# Audio_Input_Line_In.net
KiCad netlist of a schematic drawn in Altium Designer
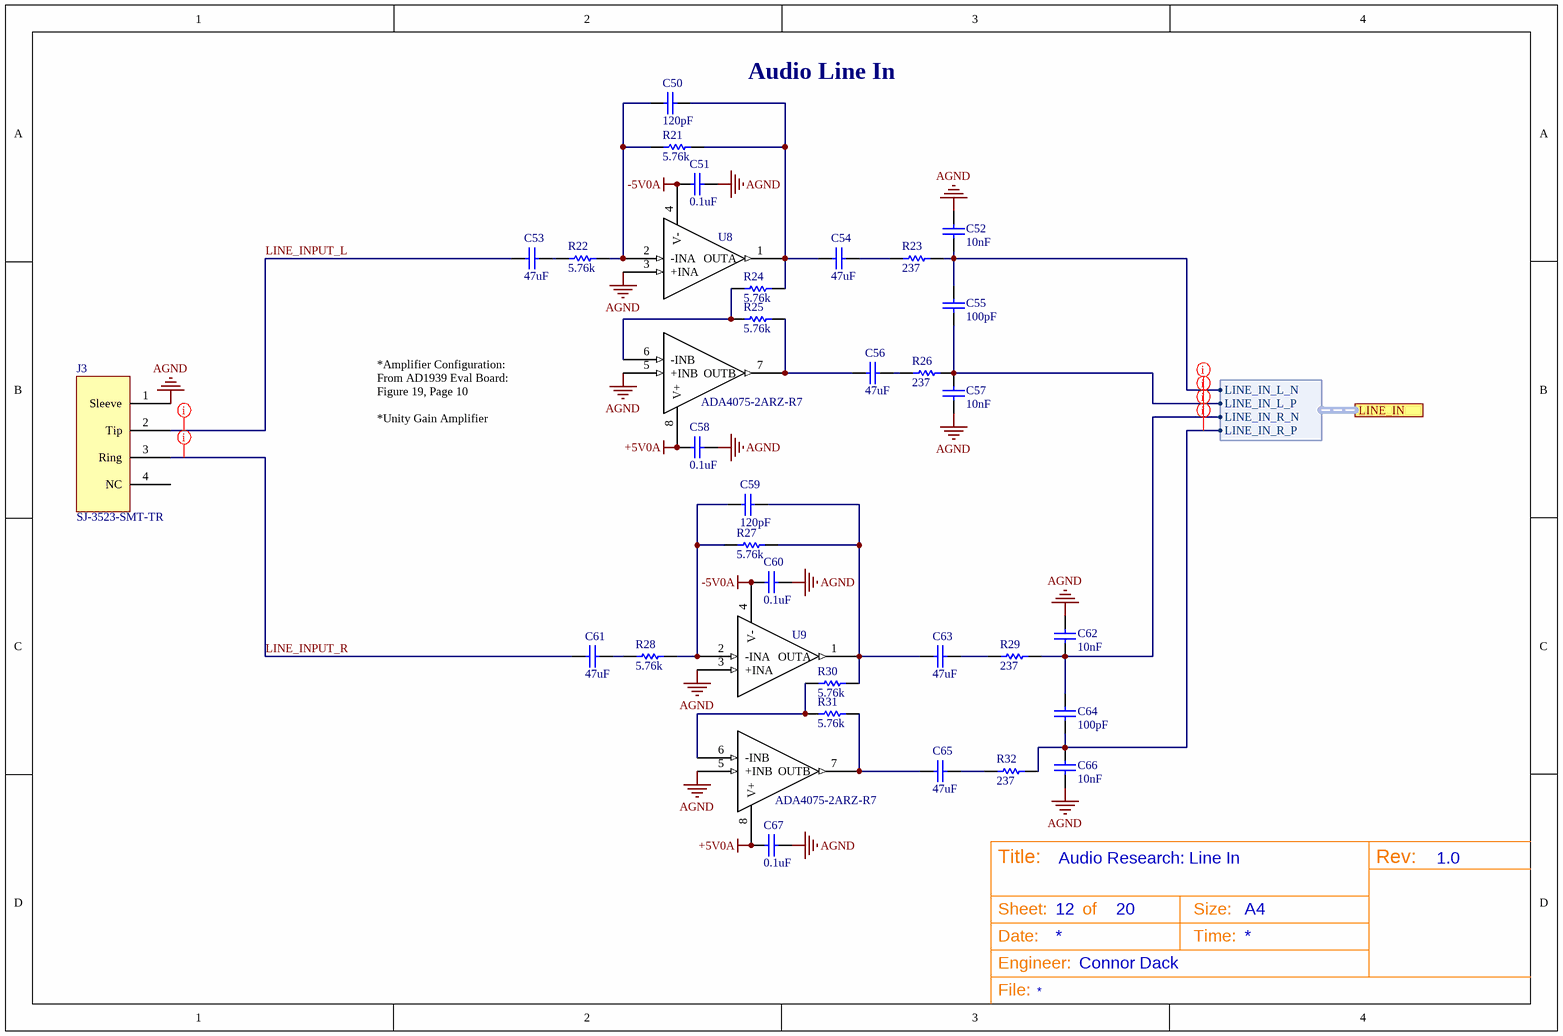
[diagram p0: Audio_Input_Line_In.SchDoc]

(export (version "E")
  (design (tool "Eeschema 10.0.6"))
  (components
    (comp (ref "C50")
      (value "CL10C121JB8NCNC")
      (footprint "3-0603_L")
      (description "120pF 50V Ceramic Capacitor C0G, NP0 0603 (1608 Metric) 0.063\" L x 0.031\" W (1.60mm x 0.80mm)")
      (fields
        (field (name "MANUFACTURER") "Samsung Electro-Mechanics America, Inc.")
        (field (name "TOLERANCE") "±5%")
        (field (name "CAPACITANCE") "120pF")
      )
      (libsource (lib "Schematic_Components") (part "CL10C121JB8NCNC"))
    )
    (comp (ref "C51")
      (value "CL10F104ZO8NNNC")
      (footprint "3-0603_L")
      (description "CAP CER 0.1UF 16V Y5V 0603")
      (fields
        (field (name "MANUFACTURER") "Samsung")
        (field (name "TOLERANCE") "80%")
        (field (name "CAPACITANCE") "0.1uF")
      )
      (libsource (lib "Schematic_Components_CD") (part "CL10F104ZO8NNNC"))
    )
    (comp (ref "C52")
      (value "~")
      (footprint "3-0603_L")
      (description "CAP CER 10000PF 200V X7R 0603")
      (fields
        (field (name "MANUFACTURER") "KEMET")
        (field (name "MANUFACTURER PART NUMBER") "C0603C103J2RACTU")
        (field (name "CAPACITANCE") "10nF")
      )
      (libsource (lib "Miscellaneous Devices") (part "C0603C103J2RACTU"))
    )
    (comp (ref "C53")
      (value "CL32A476KOJNNNE")
      (footprint "C1210X25_L")
      (description "CAP CER 47UF 16V X5R 1210")
      (fields
        (field (name "MANUFACTURER") "Samsung")
        (field (name "TOLERANCE") "10%")
        (field (name "CAPACITANCE") "47uF")
      )
      (libsource (lib "Schematic_Components_CD") (part "CL32A476KOJNNNE"))
    )
    (comp (ref "C54")
      (value "CL32A476KOJNNNE")
      (footprint "C1210X25_L")
      (description "CAP CER 47UF 16V X5R 1210")
      (fields
        (field (name "MANUFACTURER") "Samsung")
        (field (name "TOLERANCE") "10%")
        (field (name "CAPACITANCE") "47uF")
      )
      (libsource (lib "Schematic_Components_CD") (part "CL32A476KOJNNNE"))
    )
    (comp (ref "C55")
      (value "C1608C0G2A101J")
      (footprint "3-0603_L")
      (description "CAP CER 100PF 100V 5% NP0 0603")
      (fields
        (field (name "MANUFACTURER") "TDK Corporation")
        (field (name "TOLERANCE") "±5%")
        (field (name "CAPACITANCE") "100pF")
      )
      (libsource (lib "Schematic_Components") (part "C1608C0G2A101J"))
    )
    (comp (ref "C56")
      (value "CL32A476KOJNNNE")
      (footprint "C1210X25_L")
      (description "CAP CER 47UF 16V X5R 1210")
      (fields
        (field (name "MANUFACTURER") "Samsung")
        (field (name "TOLERANCE") "10%")
        (field (name "CAPACITANCE") "47uF")
      )
      (libsource (lib "Schematic_Components_CD") (part "CL32A476KOJNNNE"))
    )
    (comp (ref "C57")
      (value "~")
      (footprint "3-0603_L")
      (description "CAP CER 10000PF 200V X7R 0603")
      (fields
        (field (name "MANUFACTURER") "KEMET")
        (field (name "MANUFACTURER PART NUMBER") "C0603C103J2RACTU")
        (field (name "CAPACITANCE") "10nF")
      )
      (libsource (lib "Miscellaneous Devices") (part "C0603C103J2RACTU"))
    )
    (comp (ref "C58")
      (value "CL10F104ZO8NNNC")
      (footprint "3-0603_L")
      (description "CAP CER 0.1UF 16V Y5V 0603")
      (fields
        (field (name "MANUFACTURER") "Samsung")
        (field (name "TOLERANCE") "80%")
        (field (name "CAPACITANCE") "0.1uF")
      )
      (libsource (lib "Schematic_Components_CD") (part "CL10F104ZO8NNNC"))
    )
    (comp (ref "C59")
      (value "CL10C121JB8NCNC")
      (footprint "3-0603_L")
      (description "120pF 50V Ceramic Capacitor C0G, NP0 0603 (1608 Metric) 0.063\" L x 0.031\" W (1.60mm x 0.80mm)")
      (fields
        (field (name "MANUFACTURER") "Samsung Electro-Mechanics America, Inc.")
        (field (name "TOLERANCE") "±5%")
        (field (name "CAPACITANCE") "120pF")
      )
      (libsource (lib "Schematic_Components") (part "CL10C121JB8NCNC"))
    )
    (comp (ref "C60")
      (value "CL10F104ZO8NNNC")
      (footprint "3-0603_L")
      (description "CAP CER 0.1UF 16V Y5V 0603")
      (fields
        (field (name "MANUFACTURER") "Samsung")
        (field (name "TOLERANCE") "80%")
        (field (name "CAPACITANCE") "0.1uF")
      )
      (libsource (lib "Schematic_Components_CD") (part "CL10F104ZO8NNNC"))
    )
    (comp (ref "C61")
      (value "CL32A476KOJNNNE")
      (footprint "C1210X25_L")
      (description "CAP CER 47UF 16V X5R 1210")
      (fields
        (field (name "MANUFACTURER") "Samsung")
        (field (name "TOLERANCE") "10%")
        (field (name "CAPACITANCE") "47uF")
      )
      (libsource (lib "Schematic_Components_CD") (part "CL32A476KOJNNNE"))
    )
    (comp (ref "C62")
      (value "~")
      (footprint "3-0603_L")
      (description "CAP CER 10000PF 200V X7R 0603")
      (fields
        (field (name "MANUFACTURER") "KEMET")
        (field (name "MANUFACTURER PART NUMBER") "C0603C103J2RACTU")
        (field (name "CAPACITANCE") "10nF")
      )
      (libsource (lib "Miscellaneous Devices") (part "C0603C103J2RACTU"))
    )
    (comp (ref "C63")
      (value "CL32A476KOJNNNE")
      (footprint "C1210X25_L")
      (description "CAP CER 47UF 16V X5R 1210")
      (fields
        (field (name "MANUFACTURER") "Samsung")
        (field (name "TOLERANCE") "10%")
        (field (name "CAPACITANCE") "47uF")
      )
      (libsource (lib "Schematic_Components_CD") (part "CL32A476KOJNNNE"))
    )
    (comp (ref "C64")
      (value "C1608C0G2A101J")
      (footprint "3-0603_L")
      (description "CAP CER 100PF 100V 5% NP0 0603")
      (fields
        (field (name "MANUFACTURER") "TDK Corporation")
        (field (name "TOLERANCE") "±5%")
        (field (name "CAPACITANCE") "100pF")
      )
      (libsource (lib "Schematic_Components") (part "C1608C0G2A101J"))
    )
    (comp (ref "C65")
      (value "CL32A476KOJNNNE")
      (footprint "C1210X25_L")
      (description "CAP CER 47UF 16V X5R 1210")
      (fields
        (field (name "MANUFACTURER") "Samsung")
        (field (name "TOLERANCE") "10%")
        (field (name "CAPACITANCE") "47uF")
      )
      (libsource (lib "Schematic_Components_CD") (part "CL32A476KOJNNNE"))
    )
    (comp (ref "C66")
      (value "~")
      (footprint "3-0603_L")
      (description "CAP CER 10000PF 200V X7R 0603")
      (fields
        (field (name "MANUFACTURER") "KEMET")
        (field (name "MANUFACTURER PART NUMBER") "C0603C103J2RACTU")
        (field (name "CAPACITANCE") "10nF")
      )
      (libsource (lib "Miscellaneous Devices") (part "C0603C103J2RACTU"))
    )
    (comp (ref "C67")
      (value "CL10F104ZO8NNNC")
      (footprint "3-0603_L")
      (description "CAP CER 0.1UF 16V Y5V 0603")
      (fields
        (field (name "MANUFACTURER") "Samsung")
        (field (name "TOLERANCE") "80%")
        (field (name "CAPACITANCE") "0.1uF")
      )
      (libsource (lib "Schematic_Components_CD") (part "CL10F104ZO8NNNC"))
    )
    (comp (ref "J3")
      (value "SJ-3523-SMT-TR")
      (footprint "SJ-3523-SMT-TR")
      (description "3.50mm (0.141\", 1/8\", Mini Plug) - Headphone Phone Jack Stereo Connector Solder")
      (fields
        (field (name "MANUFACTURER") "CUI Inc.")
        (field (name "MANUFACTURER PART NUMBER") "SJ-3523-SMT-TR")
        (field (name "PUBLISHER") "Altium Limited")
      )
      (libsource (lib "NIH_DE0_Nano_Daughter_Card_Library") (part "SJ-3523-SMT-TR"))
    )
    (comp (ref "R21")
      (value "ERJ-3EKF5761V")
      (footprint "3-0603_R_L")
      (description "RES SMD 5.76K OHM 1% 1/10W 0603")
      (fields
        (field (name "MANUFACTURER") "Panasonic Electronic Components")
        (field (name "TOLERANCE") "±1%")
        (field (name "RESISTANCE (OHMS)") "5.76k")
      )
      (libsource (lib "Schematic_Components") (part "ERJ-3EKF5761V"))
    )
    (comp (ref "R22")
      (value "ERJ-3EKF5761V")
      (footprint "3-0603_R_L")
      (description "RES SMD 5.76K OHM 1% 1/10W 0603")
      (fields
        (field (name "MANUFACTURER") "Panasonic Electronic Components")
        (field (name "TOLERANCE") "±1%")
        (field (name "RESISTANCE (OHMS)") "5.76k")
      )
      (libsource (lib "Schematic_Components") (part "ERJ-3EKF5761V"))
    )
    (comp (ref "R23")
      (value "ERJ-3EKF2370V")
      (footprint "3-0603_R_L")
      (description "RES SMD 237 OHM 1% 1/10W 0603")
      (fields
        (field (name "MANUFACTURER") "Panasonic Electronic Components")
        (field (name "TOLERANCE") "±1%")
        (field (name "RESISTANCE (OHMS)") "237")
      )
      (libsource (lib "Schematic_Components") (part "ERJ-3EKF2370V"))
    )
    (comp (ref "R24")
      (value "ERJ-3EKF5761V")
      (footprint "3-0603_R_L")
      (description "RES SMD 5.76K OHM 1% 1/10W 0603")
      (fields
        (field (name "MANUFACTURER") "Panasonic Electronic Components")
        (field (name "TOLERANCE") "±1%")
        (field (name "RESISTANCE (OHMS)") "5.76k")
      )
      (libsource (lib "Schematic_Components") (part "ERJ-3EKF5761V"))
    )
    (comp (ref "R25")
      (value "ERJ-3EKF5761V")
      (footprint "3-0603_R_L")
      (description "RES SMD 5.76K OHM 1% 1/10W 0603")
      (fields
        (field (name "MANUFACTURER") "Panasonic Electronic Components")
        (field (name "TOLERANCE") "±1%")
        (field (name "RESISTANCE (OHMS)") "5.76k")
      )
      (libsource (lib "Schematic_Components") (part "ERJ-3EKF5761V"))
    )
    (comp (ref "R26")
      (value "ERJ-3EKF2370V")
      (footprint "3-0603_R_L")
      (description "RES SMD 237 OHM 1% 1/10W 0603")
      (fields
        (field (name "MANUFACTURER") "Panasonic Electronic Components")
        (field (name "TOLERANCE") "±1%")
        (field (name "RESISTANCE (OHMS)") "237")
      )
      (libsource (lib "Schematic_Components") (part "ERJ-3EKF2370V"))
    )
    (comp (ref "R27")
      (value "ERJ-3EKF5761V")
      (footprint "3-0603_R_L")
      (description "RES SMD 5.76K OHM 1% 1/10W 0603")
      (fields
        (field (name "MANUFACTURER") "Panasonic Electronic Components")
        (field (name "TOLERANCE") "±1%")
        (field (name "RESISTANCE (OHMS)") "5.76k")
      )
      (libsource (lib "Schematic_Components") (part "ERJ-3EKF5761V"))
    )
    (comp (ref "R28")
      (value "ERJ-3EKF5761V")
      (footprint "3-0603_R_L")
      (description "RES SMD 5.76K OHM 1% 1/10W 0603")
      (fields
        (field (name "MANUFACTURER") "Panasonic Electronic Components")
        (field (name "TOLERANCE") "±1%")
        (field (name "RESISTANCE (OHMS)") "5.76k")
      )
      (libsource (lib "Schematic_Components") (part "ERJ-3EKF5761V"))
    )
    (comp (ref "R29")
      (value "ERJ-3EKF2370V")
      (footprint "3-0603_R_L")
      (description "RES SMD 237 OHM 1% 1/10W 0603")
      (fields
        (field (name "MANUFACTURER") "Panasonic Electronic Components")
        (field (name "TOLERANCE") "±1%")
        (field (name "RESISTANCE (OHMS)") "237")
      )
      (libsource (lib "Schematic_Components") (part "ERJ-3EKF2370V"))
    )
    (comp (ref "R30")
      (value "ERJ-3EKF5761V")
      (footprint "3-0603_R_L")
      (description "RES SMD 5.76K OHM 1% 1/10W 0603")
      (fields
        (field (name "MANUFACTURER") "Panasonic Electronic Components")
        (field (name "TOLERANCE") "±1%")
        (field (name "RESISTANCE (OHMS)") "5.76k")
      )
      (libsource (lib "Schematic_Components") (part "ERJ-3EKF5761V"))
    )
    (comp (ref "R31")
      (value "ERJ-3EKF5761V")
      (footprint "3-0603_R_L")
      (description "RES SMD 5.76K OHM 1% 1/10W 0603")
      (fields
        (field (name "MANUFACTURER") "Panasonic Electronic Components")
        (field (name "TOLERANCE") "±1%")
        (field (name "RESISTANCE (OHMS)") "5.76k")
      )
      (libsource (lib "Schematic_Components") (part "ERJ-3EKF5761V"))
    )
    (comp (ref "R32")
      (value "ERJ-3EKF2370V")
      (footprint "3-0603_R_L")
      (description "RES SMD 237 OHM 1% 1/10W 0603")
      (fields
        (field (name "MANUFACTURER") "Panasonic Electronic Components")
        (field (name "TOLERANCE") "±1%")
        (field (name "RESISTANCE (OHMS)") "237")
      )
      (libsource (lib "Schematic_Components") (part "ERJ-3EKF2370V"))
    )
    (comp (ref "U8")
      (value "ADA4075-2ARZ-R7")
      (footprint "SOIC127P600X175-8L")
      (description "IC OPAMP GP 6.5MHZ 8SOIC")
      (fields
        (field (name "MANUFACTURER") "Analog Devices Inc.")
        (field (name "MANUFACTURER PART NUMBER") "ADA4075-2ARZ-R7")
      )
      (libsource (lib "Schematic_Components_CD") (part "ADA4075-2ARZ-R7"))
    )
    (comp (ref "U9")
      (value "ADA4075-2ARZ-R7")
      (footprint "SOIC127P600X175-8L")
      (description "IC OPAMP GP 6.5MHZ 8SOIC")
      (fields
        (field (name "MANUFACTURER") "Analog Devices Inc.")
        (field (name "MANUFACTURER PART NUMBER") "ADA4075-2ARZ-R7")
      )
      (libsource (lib "Schematic_Components_CD") (part "ADA4075-2ARZ-R7"))
    )
  )
  (nets
    (net (code "2") (name "+5V0A") (class "Default")
      (node (ref "C58") (pin "2") (pinfunction "2_2") (pintype "passive"))
      (node (ref "C67") (pin "2") (pinfunction "2_2") (pintype "passive"))
      (node (ref "U8") (pin "8") (pinfunction "V+_8") (pintype "passive"))
      (node (ref "U9") (pin "8") (pinfunction "V+_8") (pintype "passive"))
    )
    (net (code "3") (name "-5V0A") (class "Default")
      (node (ref "C51") (pin "2") (pinfunction "2_2") (pintype "passive"))
      (node (ref "C60") (pin "2") (pinfunction "2_2") (pintype "passive"))
      (node (ref "U8") (pin "4") (pinfunction "V-_4") (pintype "passive"))
      (node (ref "U9") (pin "4") (pinfunction "V-_4") (pintype "passive"))
    )
    (net (code "4") (name "/LINE_INPUT_L") (class "Default")
      (node (ref "C53") (pin "1") (pinfunction "1_1") (pintype "passive"))
      (node (ref "J3") (pin "2") (pinfunction "Tip_2") (pintype "passive"))
    )
    (net (code "5") (name "/LINE_INPUT_R") (class "Default")
      (node (ref "C61") (pin "1") (pinfunction "1_1") (pintype "passive"))
      (node (ref "J3") (pin "3") (pinfunction "Ring_3") (pintype "passive"))
    )
    (net (code "7") (name "AGND") (class "Default")
      (node (ref "C51") (pin "1") (pinfunction "1_1") (pintype "passive"))
      (node (ref "C52") (pin "2") (pinfunction "2_2") (pintype "passive"))
      (node (ref "C57") (pin "1") (pinfunction "1_1") (pintype "passive"))
      (node (ref "C58") (pin "1") (pinfunction "1_1") (pintype "passive"))
      (node (ref "C60") (pin "1") (pinfunction "1_1") (pintype "passive"))
      (node (ref "C62") (pin "2") (pinfunction "2_2") (pintype "passive"))
      (node (ref "C66") (pin "1") (pinfunction "1_1") (pintype "passive"))
      (node (ref "C67") (pin "1") (pinfunction "1_1") (pintype "passive"))
      (node (ref "J3") (pin "1") (pinfunction "Sleeve_1") (pintype "passive"))
      (node (ref "U8") (pin "3") (pinfunction "+INA_3") (pintype "input"))
      (node (ref "U8") (pin "5") (pinfunction "+INB_5") (pintype "input"))
      (node (ref "U9") (pin "3") (pinfunction "+INA_3") (pintype "input"))
      (node (ref "U9") (pin "5") (pinfunction "+INB_5") (pintype "input"))
    )
    (net (code "8") (name "Net-(C52-Pad1)") (class "Default")
      (node (ref "C52") (pin "1") (pinfunction "1_1") (pintype "passive"))
      (node (ref "C55") (pin "2") (pinfunction "2_2") (pintype "passive"))
      (node (ref "R23") (pin "2") (pinfunction "2_2") (pintype "passive"))
    )
    (net (code "9") (name "Net-(C53-Pad2)") (class "Default")
      (node (ref "C53") (pin "2") (pinfunction "2_2") (pintype "passive"))
      (node (ref "R22") (pin "1") (pinfunction "1_1") (pintype "passive"))
    )
    (net (code "10") (name "Net-(C54-Pad2)") (class "Default")
      (node (ref "C54") (pin "2") (pinfunction "2_2") (pintype "passive"))
      (node (ref "R23") (pin "1") (pinfunction "1_1") (pintype "passive"))
    )
    (net (code "11") (name "Net-(C55-Pad1)") (class "Default")
      (node (ref "C55") (pin "1") (pinfunction "1_1") (pintype "passive"))
      (node (ref "C57") (pin "2") (pinfunction "2_2") (pintype "passive"))
      (node (ref "R26") (pin "2") (pinfunction "2_2") (pintype "passive"))
    )
    (net (code "12") (name "Net-(C56-Pad2)") (class "Default")
      (node (ref "C56") (pin "2") (pinfunction "2_2") (pintype "passive"))
      (node (ref "R26") (pin "1") (pinfunction "1_1") (pintype "passive"))
    )
    (net (code "13") (name "Net-(C61-Pad2)") (class "Default")
      (node (ref "C61") (pin "2") (pinfunction "2_2") (pintype "passive"))
      (node (ref "R28") (pin "1") (pinfunction "1_1") (pintype "passive"))
    )
    (net (code "14") (name "Net-(C62-Pad1)") (class "Default")
      (node (ref "C62") (pin "1") (pinfunction "1_1") (pintype "passive"))
      (node (ref "C64") (pin "2") (pinfunction "2_2") (pintype "passive"))
      (node (ref "R29") (pin "2") (pinfunction "2_2") (pintype "passive"))
    )
    (net (code "15") (name "Net-(C63-Pad2)") (class "Default")
      (node (ref "C63") (pin "2") (pinfunction "2_2") (pintype "passive"))
      (node (ref "R29") (pin "1") (pinfunction "1_1") (pintype "passive"))
    )
    (net (code "16") (name "Net-(C64-Pad1)") (class "Default")
      (node (ref "C64") (pin "1") (pinfunction "1_1") (pintype "passive"))
      (node (ref "C66") (pin "2") (pinfunction "2_2") (pintype "passive"))
      (node (ref "R32") (pin "2") (pinfunction "2_2") (pintype "passive"))
    )
    (net (code "17") (name "Net-(C65-Pad2)") (class "Default")
      (node (ref "C65") (pin "2") (pinfunction "2_2") (pintype "passive"))
      (node (ref "R32") (pin "1") (pinfunction "1_1") (pintype "passive"))
    )
    (net (code "18") (name "Net-(U8--INA)") (class "Default")
      (node (ref "C50") (pin "1") (pinfunction "1_1") (pintype "passive"))
      (node (ref "R21") (pin "1") (pinfunction "1_1") (pintype "passive"))
      (node (ref "R22") (pin "2") (pinfunction "2_2") (pintype "passive"))
      (node (ref "U8") (pin "2") (pinfunction "-INA_2") (pintype "input"))
    )
    (net (code "19") (name "Net-(U8--INB)") (class "Default")
      (node (ref "R24") (pin "2") (pinfunction "2_2") (pintype "passive"))
      (node (ref "R25") (pin "1") (pinfunction "1_1") (pintype "passive"))
      (node (ref "U8") (pin "6") (pinfunction "-INB_6") (pintype "input"))
    )
    (net (code "20") (name "Net-(U8-OUTA)") (class "Default")
      (node (ref "C50") (pin "2") (pinfunction "2_2") (pintype "passive"))
      (node (ref "C54") (pin "1") (pinfunction "1_1") (pintype "passive"))
      (node (ref "R21") (pin "2") (pinfunction "2_2") (pintype "passive"))
      (node (ref "R24") (pin "1") (pinfunction "1_1") (pintype "passive"))
      (node (ref "U8") (pin "1") (pinfunction "OUTA_1") (pintype "output"))
    )
    (net (code "21") (name "Net-(U8-OUTB)") (class "Default")
      (node (ref "C56") (pin "1") (pinfunction "1_1") (pintype "passive"))
      (node (ref "R25") (pin "2") (pinfunction "2_2") (pintype "passive"))
      (node (ref "U8") (pin "7") (pinfunction "OUTB_7") (pintype "output"))
    )
    (net (code "22") (name "Net-(U9--INA)") (class "Default")
      (node (ref "C59") (pin "1") (pinfunction "1_1") (pintype "passive"))
      (node (ref "R27") (pin "1") (pinfunction "1_1") (pintype "passive"))
      (node (ref "R28") (pin "2") (pinfunction "2_2") (pintype "passive"))
      (node (ref "U9") (pin "2") (pinfunction "-INA_2") (pintype "input"))
    )
    (net (code "23") (name "Net-(U9--INB)") (class "Default")
      (node (ref "R30") (pin "1") (pinfunction "1_1") (pintype "passive"))
      (node (ref "R31") (pin "1") (pinfunction "1_1") (pintype "passive"))
      (node (ref "U9") (pin "6") (pinfunction "-INB_6") (pintype "input"))
    )
    (net (code "24") (name "Net-(U9-OUTA)") (class "Default")
      (node (ref "C59") (pin "2") (pinfunction "2_2") (pintype "passive"))
      (node (ref "C63") (pin "1") (pinfunction "1_1") (pintype "passive"))
      (node (ref "R27") (pin "2") (pinfunction "2_2") (pintype "passive"))
      (node (ref "R30") (pin "2") (pinfunction "2_2") (pintype "passive"))
      (node (ref "U9") (pin "1") (pinfunction "OUTA_1") (pintype "output"))
    )
    (net (code "25") (name "Net-(U9-OUTB)") (class "Default")
      (node (ref "C65") (pin "1") (pinfunction "1_1") (pintype "passive"))
      (node (ref "R31") (pin "2") (pinfunction "2_2") (pintype "passive"))
      (node (ref "U9") (pin "7") (pinfunction "OUTB_7") (pintype "output"))
    )
    (net (code "26") (name "unconnected-(J3-NC-Pad4)") (class "Default")
      (node (ref "J3") (pin "4") (pinfunction "NC_4") (pintype "passive"))
    )
  )
)
